# rover.net
KiCad netlist of a schematic drawn in EAGLE
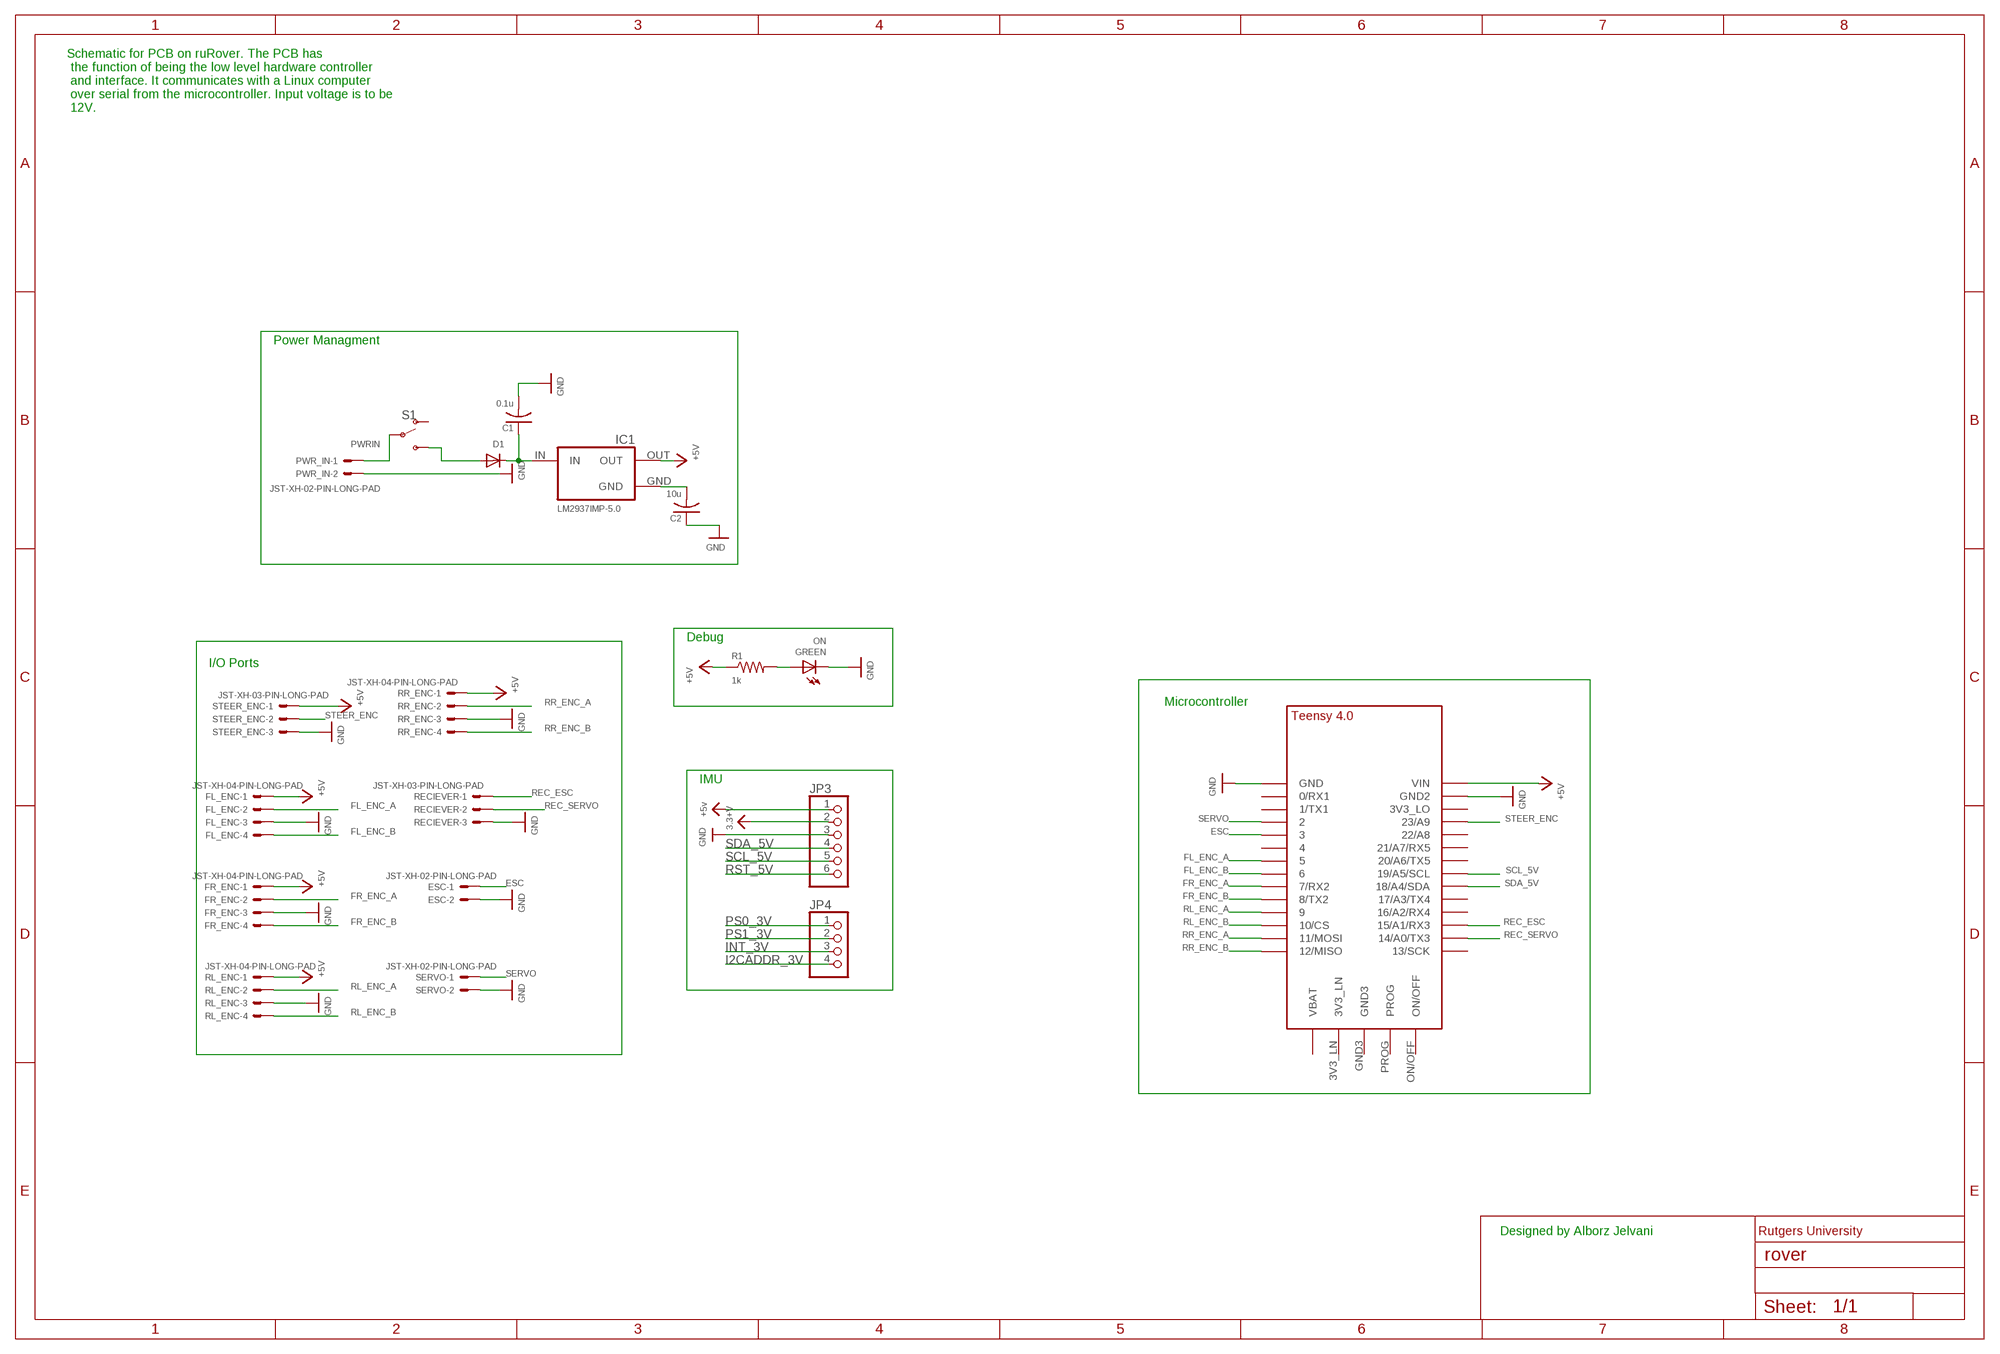
[diagram p0: schematic, sheet 1]

(export (version "E")
  (design (tool "Eeschema 10.0.6"))
  (components
    (comp (ref "C1")
      (value "0.1u")
      (footprint "eagle-import:C1206")
      (libsource (lib "eagle-import") (part "C-USC1206"))
    )
    (comp (ref "C2")
      (value "10u")
      (footprint "eagle-import:C1206")
      (libsource (lib "eagle-import") (part "C-USC1206"))
    )
    (comp (ref "D1")
      (value "DIODESMA")
      (footprint "eagle-import:SMADIODE")
      (libsource (lib "eagle-import") (part "DIODESMA"))
    )
    (comp (ref "ESC")
      (value "JST-XH-02-PIN-LONG-PAD")
      (footprint "eagle-import:JST-XH-02-PACKAGE-LONG-PAD")
      (libsource (lib "eagle-import") (part "JST-XH-02-PIN-LONG-PAD"))
    )
    (comp (ref "FL_ENC")
      (value "JST-XH-04-PIN-LONG-PAD")
      (footprint "eagle-import:JST-XH-04-PACKAGE-LONG-PAD")
      (libsource (lib "eagle-import") (part "JST-XH-04-PIN-LONG-PAD"))
    )
    (comp (ref "FR_ENC")
      (value "JST-XH-04-PIN-LONG-PAD")
      (footprint "eagle-import:JST-XH-04-PACKAGE-LONG-PAD")
      (libsource (lib "eagle-import") (part "JST-XH-04-PIN-LONG-PAD"))
    )
    (comp (ref "GREEN")
      (value "ON")
      (footprint "eagle-import:CHIP-LED0805")
      (libsource (lib "eagle-import") (part "LEDCHIP-LED0805"))
    )
    (comp (ref "IC1")
      (value "LM2937IMP-5.0")
      (footprint "eagle-import:SOT223")
      (libsource (lib "eagle-import") (part "LM2937IMP-5.0"))
    )
    (comp (ref "JP3")
      (value "HEADER-1X676MIL")
      (footprint "eagle-import:1X06_ROUND_76")
      (libsource (lib "eagle-import") (part "HEADER-1X676MIL"))
    )
    (comp (ref "JP4")
      (value "HEADER-1X476MIL")
      (footprint "eagle-import:1X04_ROUND_76")
      (libsource (lib "eagle-import") (part "HEADER-1X476MIL"))
    )
    (comp (ref "PWR_IN")
      (value "JST-XH-02-PIN-LONG-PAD")
      (footprint "eagle-import:JST-XH-02-PACKAGE-LONG-PAD")
      (libsource (lib "eagle-import") (part "JST-XH-02-PIN-LONG-PAD"))
    )
    (comp (ref "R1")
      (value "1k")
      (footprint "eagle-import:R0603")
      (libsource (lib "eagle-import") (part "R-US_R0603"))
    )
    (comp (ref "RECIEVER")
      (value "JST-XH-03-PIN-LONG-PAD")
      (footprint "eagle-import:JST-XH-03-PACKAGE-LONG-PAD")
      (libsource (lib "eagle-import") (part "JST-XH-03-PIN-LONG-PAD"))
    )
    (comp (ref "RL_ENC")
      (value "JST-XH-04-PIN-LONG-PAD")
      (footprint "eagle-import:JST-XH-04-PACKAGE-LONG-PAD")
      (libsource (lib "eagle-import") (part "JST-XH-04-PIN-LONG-PAD"))
    )
    (comp (ref "RR_ENC")
      (value "JST-XH-04-PIN-LONG-PAD")
      (footprint "eagle-import:JST-XH-04-PACKAGE-LONG-PAD")
      (libsource (lib "eagle-import") (part "JST-XH-04-PIN-LONG-PAD"))
    )
    (comp (ref "S1")
      (value "SWITCH-SPDT-SMD-AYZ0202")
      (footprint "eagle-import:SWITCH_DPDT_SMD_AYZ0202")
      (libsource (lib "eagle-import") (part "SWITCH-SPDT-SMD-AYZ0202"))
    )
    (comp (ref "SERVO")
      (value "JST-XH-02-PIN-LONG-PAD")
      (footprint "eagle-import:JST-XH-02-PACKAGE-LONG-PAD")
      (libsource (lib "eagle-import") (part "JST-XH-02-PIN-LONG-PAD"))
    )
    (comp (ref "STEER_ENC")
      (value "JST-XH-03-PIN-LONG-PAD")
      (footprint "eagle-import:JST-XH-03-PACKAGE-LONG-PAD")
      (libsource (lib "eagle-import") (part "JST-XH-03-PIN-LONG-PAD"))
    )
    (comp (ref "U$5")
      (value "TEENSY_4.0-BASIC")
      (footprint "eagle-import:TEENSY_4.0-BASIC")
      (libsource (lib "eagle-import") (part "TEENSY_4.0-BASIC"))
    )
  )
  (nets
    (net (code "1") (name "+5V") (class "Default")
      (node (ref "FL_ENC") (pin "1") (pinfunction "S_1") (pintype "passive"))
      (node (ref "FR_ENC") (pin "1") (pinfunction "S_1") (pintype "passive"))
      (node (ref "IC1") (pin "OUT") (pinfunction "OUT_OUT") (pintype "output"))
      (node (ref "JP3") (pin "1") (pinfunction "1_1") (pintype "passive"))
      (node (ref "R1") (pin "1") (pinfunction "1_1") (pintype "passive"))
      (node (ref "RL_ENC") (pin "1") (pinfunction "S_1") (pintype "passive"))
      (node (ref "RR_ENC") (pin "1") (pinfunction "S_1") (pintype "passive"))
      (node (ref "STEER_ENC") (pin "1") (pinfunction "S_1") (pintype "passive"))
      (node (ref "U$5") (pin "VIN") (pinfunction "VIN_VIN") (pintype "bidirectional"))
    )
    (net (code "2") (name "/ESC") (class "Default")
      (node (ref "ESC") (pin "1") (pinfunction "S_1") (pintype "passive"))
      (node (ref "U$5") (pin "3/CANTX") (pinfunction "3_3/CANTX") (pintype "bidirectional"))
    )
    (net (code "3") (name "/FL_ENC_A") (class "Default")
      (node (ref "FL_ENC") (pin "2") (pinfunction "S_2") (pintype "passive"))
      (node (ref "U$5") (pin "5") (pinfunction "5_5") (pintype "bidirectional"))
    )
    (net (code "4") (name "/FL_ENC_B") (class "Default")
      (node (ref "FL_ENC") (pin "4") (pinfunction "S_4") (pintype "passive"))
      (node (ref "U$5") (pin "6") (pinfunction "6_6") (pintype "bidirectional"))
    )
    (net (code "5") (name "/FR_ENC_A") (class "Default")
      (node (ref "FR_ENC") (pin "2") (pinfunction "S_2") (pintype "passive"))
      (node (ref "U$5") (pin "7") (pinfunction "7/RX2_7") (pintype "bidirectional"))
    )
    (net (code "6") (name "/FR_ENC_B") (class "Default")
      (node (ref "FR_ENC") (pin "4") (pinfunction "S_4") (pintype "passive"))
      (node (ref "U$5") (pin "8") (pinfunction "8/TX2_8") (pintype "bidirectional"))
    )
    (net (code "7") (name "/I2CADDR_3V") (class "Default")
      (node (ref "JP4") (pin "4") (pinfunction "4_4") (pintype "passive"))
    )
    (net (code "8") (name "/INT_3V") (class "Default")
      (node (ref "JP4") (pin "3") (pinfunction "3_3") (pintype "passive"))
    )
    (net (code "9") (name "/PS0_3V") (class "Default")
      (node (ref "JP4") (pin "1") (pinfunction "1_1") (pintype "passive"))
    )
    (net (code "10") (name "/PS1_3V") (class "Default")
      (node (ref "JP4") (pin "2") (pinfunction "2_2") (pintype "passive"))
    )
    (net (code "11") (name "/PWRIN") (class "Default")
      (node (ref "PWR_IN") (pin "1") (pinfunction "S_1") (pintype "passive"))
      (node (ref "S1") (pin "2") (pinfunction "P_2") (pintype "passive"))
    )
    (net (code "12") (name "/REC_ESC") (class "Default")
      (node (ref "RECIEVER") (pin "1") (pinfunction "S_1") (pintype "passive"))
      (node (ref "U$5") (pin "15/A1") (pinfunction "15/A1/RX3_15/A1") (pintype "bidirectional"))
    )
    (net (code "13") (name "/REC_SERVO") (class "Default")
      (node (ref "RECIEVER") (pin "2") (pinfunction "S_2") (pintype "passive"))
      (node (ref "U$5") (pin "14/A0") (pinfunction "14/A0/TX3_14/A0") (pintype "bidirectional"))
    )
    (net (code "14") (name "/RL_ENC_A") (class "Default")
      (node (ref "RL_ENC") (pin "2") (pinfunction "S_2") (pintype "passive"))
      (node (ref "U$5") (pin "9/CS") (pinfunction "9_9/CS") (pintype "bidirectional"))
    )
    (net (code "15") (name "/RL_ENC_B") (class "Default")
      (node (ref "RL_ENC") (pin "4") (pinfunction "S_4") (pintype "passive"))
      (node (ref "U$5") (pin "10/CS") (pinfunction "10/CS_10/CS") (pintype "bidirectional"))
    )
    (net (code "16") (name "/RR_ENC_A") (class "Default")
      (node (ref "RR_ENC") (pin "2") (pinfunction "S_2") (pintype "passive"))
      (node (ref "U$5") (pin "11/MOSI") (pinfunction "11/MOSI_11/MOSI") (pintype "bidirectional"))
    )
    (net (code "17") (name "/RR_ENC_B") (class "Default")
      (node (ref "RR_ENC") (pin "4") (pinfunction "S_4") (pintype "passive"))
      (node (ref "U$5") (pin "12/MISO") (pinfunction "12/MISO_12/MISO") (pintype "bidirectional"))
    )
    (net (code "18") (name "/RST_5V") (class "Default")
      (node (ref "JP3") (pin "6") (pinfunction "6_6") (pintype "passive"))
    )
    (net (code "19") (name "/SCL_5V") (class "Default")
      (node (ref "JP3") (pin "5") (pinfunction "5_5") (pintype "passive"))
      (node (ref "U$5") (pin "19/A5/SCL") (pinfunction "19/A5/SCL_19/A5/SCL") (pintype "bidirectional"))
    )
    (net (code "20") (name "/SDA_5V") (class "Default")
      (node (ref "JP3") (pin "4") (pinfunction "4_4") (pintype "passive"))
      (node (ref "U$5") (pin "18/A4/SDA") (pinfunction "18/A4/SDA_18/A4/SDA") (pintype "bidirectional"))
    )
    (net (code "21") (name "/SERVO") (class "Default")
      (node (ref "SERVO") (pin "1") (pinfunction "S_1") (pintype "passive"))
      (node (ref "U$5") (pin "2") (pinfunction "2_2") (pintype "bidirectional"))
    )
    (net (code "22") (name "/STEER_ENC") (class "Default")
      (node (ref "STEER_ENC") (pin "2") (pinfunction "S_2") (pintype "passive"))
      (node (ref "U$5") (pin "23/A9") (pinfunction "23/A9_23/A9") (pintype "bidirectional"))
    )
    (net (code "23") (name "3.3+V") (class "Default")
      (node (ref "JP3") (pin "2") (pinfunction "2_2") (pintype "passive"))
    )
    (net (code "24") (name "GND") (class "Default")
      (node (ref "C1") (pin "2") (pinfunction "2_2") (pintype "passive"))
      (node (ref "C2") (pin "1") (pinfunction "1_1") (pintype "passive"))
      (node (ref "ESC") (pin "2") (pinfunction "S_2") (pintype "passive"))
      (node (ref "FL_ENC") (pin "3") (pinfunction "S_3") (pintype "passive"))
      (node (ref "FR_ENC") (pin "3") (pinfunction "S_3") (pintype "passive"))
      (node (ref "GREEN") (pin "C") (pinfunction "C_C") (pintype "passive"))
      (node (ref "JP3") (pin "3") (pinfunction "3_3") (pintype "passive"))
      (node (ref "PWR_IN") (pin "2") (pinfunction "S_2") (pintype "passive"))
      (node (ref "RECIEVER") (pin "3") (pinfunction "S_3") (pintype "passive"))
      (node (ref "RL_ENC") (pin "3") (pinfunction "S_3") (pintype "passive"))
      (node (ref "RR_ENC") (pin "3") (pinfunction "S_3") (pintype "passive"))
      (node (ref "SERVO") (pin "2") (pinfunction "S_2") (pintype "passive"))
      (node (ref "STEER_ENC") (pin "3") (pinfunction "S_3") (pintype "passive"))
      (node (ref "U$5") (pin "GND") (pinfunction "GND_GND") (pintype "bidirectional"))
      (node (ref "U$5") (pin "GND2") (pinfunction "GND2_GND2") (pintype "bidirectional"))
    )
    (net (code "25") (name "Net-(C1-Pad1)") (class "Default")
      (node (ref "C1") (pin "1") (pinfunction "1_1") (pintype "passive"))
      (node (ref "D1") (pin "C") (pinfunction "C_C") (pintype "passive"))
      (node (ref "IC1") (pin "IN") (pinfunction "IN_IN") (pintype "input"))
    )
    (net (code "26") (name "Net-(C2-Pad2)") (class "Default")
      (node (ref "C2") (pin "2") (pinfunction "2_2") (pintype "passive"))
      (node (ref "IC1") (pin "GND") (pinfunction "GND_GND") (pintype "power_in"))
    )
    (net (code "27") (name "Net-(GREEN-PadA)") (class "Default")
      (node (ref "GREEN") (pin "A") (pinfunction "A_A") (pintype "passive"))
      (node (ref "R1") (pin "2") (pinfunction "2_2") (pintype "passive"))
    )
    (net (code "28") (name "Net-(S1-S)") (class "Default")
      (node (ref "D1") (pin "A") (pinfunction "A_A") (pintype "passive"))
      (node (ref "S1") (pin "3") (pinfunction "S_3") (pintype "passive"))
    )
    (net (code "29") (name "unconnected-(S1-O-Pad1)") (class "Default")
      (node (ref "S1") (pin "1") (pinfunction "O_1") (pintype "passive"))
    )
    (net (code "30") (name "unconnected-(U$5-0{slash}RX1-Pad0{slash}RX)") (class "Default")
      (node (ref "U$5") (pin "0/RX") (pinfunction "0/RX1_0/RX") (pintype "bidirectional"))
    )
    (net (code "31") (name "unconnected-(U$5-1{slash}TX1-Pad1{slash}TX)") (class "Default")
      (node (ref "U$5") (pin "1/TX") (pinfunction "1/TX1_1/TX") (pintype "bidirectional"))
    )
    (net (code "32") (name "unconnected-(U$5-4-Pad4{slash}CANRX)") (class "Default")
      (node (ref "U$5") (pin "4/CANRX") (pinfunction "4_4/CANRX") (pintype "bidirectional"))
    )
    (net (code "33") (name "unconnected-(U$5-16{slash}A2{slash}RX4-Pad16{slash}A2)") (class "Default")
      (node (ref "U$5") (pin "16/A2") (pinfunction "16/A2/RX4_16/A2") (pintype "bidirectional"))
    )
    (net (code "34") (name "unconnected-(U$5-17{slash}A3{slash}TX4-Pad17{slash}A3)") (class "Default")
      (node (ref "U$5") (pin "17/A3") (pinfunction "17/A3/TX4_17/A3") (pintype "bidirectional"))
    )
    (net (code "35") (name "unconnected-(U$5-20{slash}A6{slash}TX5-Pad20{slash}A6)") (class "Default")
      (node (ref "U$5") (pin "20/A6") (pinfunction "20/A6/TX5_20/A6") (pintype "bidirectional"))
    )
    (net (code "36") (name "unconnected-(U$5-21{slash}A7{slash}RX5-Pad21{slash}A7)") (class "Default")
      (node (ref "U$5") (pin "21/A7") (pinfunction "21/A7/RX5_21/A7") (pintype "bidirectional"))
    )
    (net (code "37") (name "unconnected-(U$5-Pad3V3_LN)") (class "Default")
      (node (ref "U$5") (pin "3V3_LN") (pinfunction "3V3_LN_3V3_LN") (pintype "bidirectional"))
    )
    (net (code "38") (name "unconnected-(U$5-Pad3V3_LO)") (class "Default")
      (node (ref "U$5") (pin "3V3_LO") (pinfunction "3V3_LO_3V3_LO") (pintype "bidirectional"))
    )
    (net (code "39") (name "unconnected-(U$5-Pad13{slash}SCK)") (class "Default")
      (node (ref "U$5") (pin "13/SCK") (pinfunction "13/SCK_13/SCK") (pintype "bidirectional"))
    )
    (net (code "40") (name "unconnected-(U$5-Pad22{slash}A8)") (class "Default")
      (node (ref "U$5") (pin "22/A8") (pinfunction "22/A8_22/A8") (pintype "bidirectional"))
    )
    (net (code "41") (name "unconnected-(U$5-PadGND3)") (class "Default")
      (node (ref "U$5") (pin "GND3") (pinfunction "GND3_GND3") (pintype "bidirectional"))
    )
    (net (code "42") (name "unconnected-(U$5-PadON{slash}OFF)") (class "Default")
      (node (ref "U$5") (pin "ON/OFF") (pinfunction "ON/OFF_ON/OFF") (pintype "bidirectional"))
    )
    (net (code "43") (name "unconnected-(U$5-PadPROG)") (class "Default")
      (node (ref "U$5") (pin "PROG") (pinfunction "PROG_PROG") (pintype "bidirectional"))
    )
    (net (code "44") (name "unconnected-(U$5-VBAT-PadVBAT\\)") (class "Default")
      (node (ref "U$5") (pin "VBAT\\") (pinfunction "VBAT_VBAT\\") (pintype "bidirectional"))
    )
  )
)
